# DevBit-MAX30102.net
KiCad netlist of a schematic drawn in EAGLE
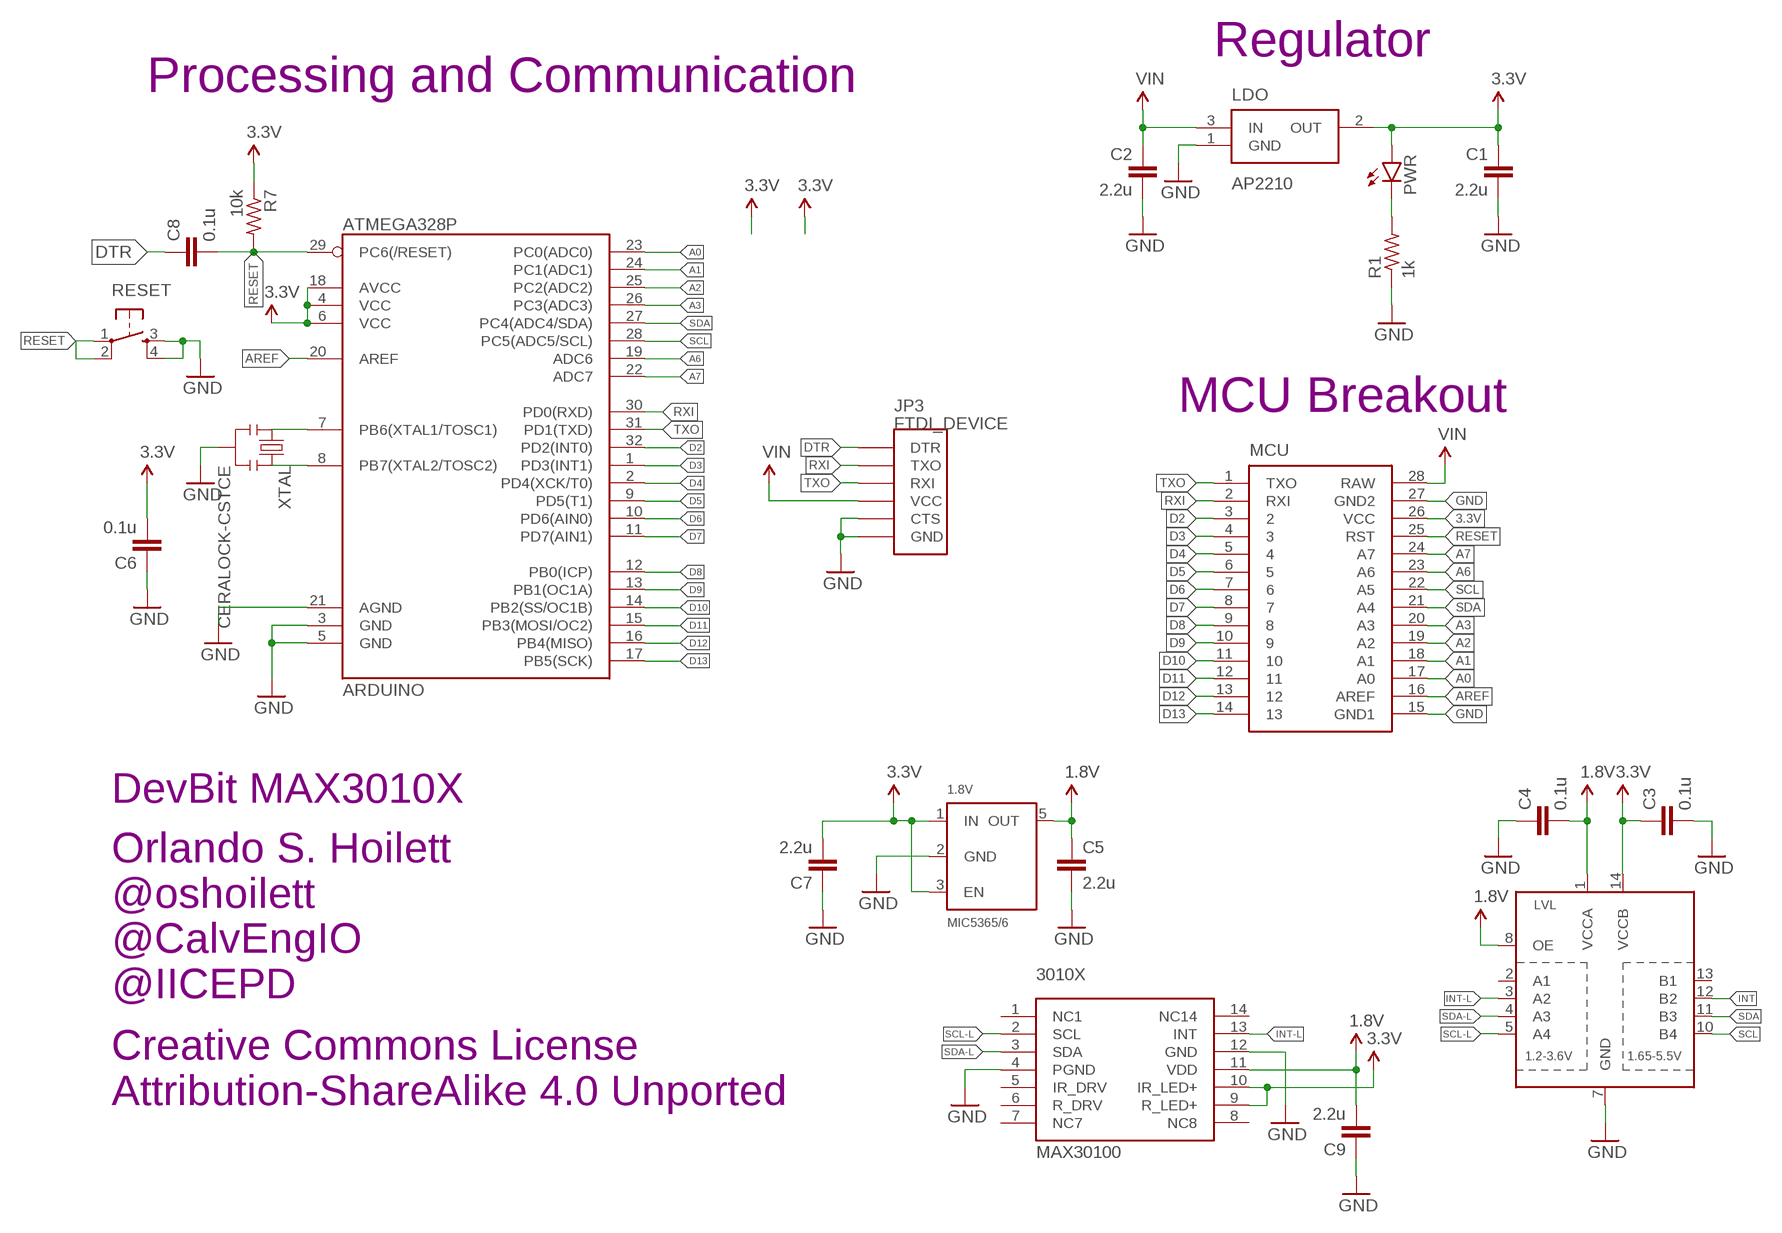
[diagram p0: schematic, sheet 1]

(export (version "E")
  (design (tool "Eeschema 10.0.6"))
  (components
    (comp (ref "1.8V")
      (value "MIC5365/6")
      (footprint "eagle-import:SC-70-5")
      (libsource (lib "eagle-import") (part "MIC5365/6"))
    )
    (comp (ref "3010X")
      (value "MAX30100")
      (footprint "eagle-import:OESIP14")
      (libsource (lib "eagle-import") (part "MAX30100"))
    )
    (comp (ref "ARDUINO")
      (value "ATMEGA328P")
      (footprint "eagle-import:TQFP32-08")
      (libsource (lib "eagle-import") (part "ATMEGA328_SMT-OHMOD"))
    )
    (comp (ref "C1")
      (value "2.2u")
      (footprint "eagle-import:C0402")
      (libsource (lib "eagle-import") (part "C-EUC0402"))
    )
    (comp (ref "C2")
      (value "2.2u")
      (footprint "eagle-import:C0402")
      (libsource (lib "eagle-import") (part "C-EUC0402"))
    )
    (comp (ref "C3")
      (value "0.1u")
      (footprint "eagle-import:C0402")
      (libsource (lib "eagle-import") (part "C-EUC0402"))
    )
    (comp (ref "C4")
      (value "0.1u")
      (footprint "eagle-import:C0402")
      (libsource (lib "eagle-import") (part "C-EUC0402"))
    )
    (comp (ref "C5")
      (value "2.2u")
      (footprint "eagle-import:C0402")
      (libsource (lib "eagle-import") (part "C-EUC0402"))
    )
    (comp (ref "C6")
      (value "0.1u")
      (footprint "eagle-import:C0402")
      (libsource (lib "eagle-import") (part "C-EUC0402"))
    )
    (comp (ref "C7")
      (value "2.2u")
      (footprint "eagle-import:C0402")
      (libsource (lib "eagle-import") (part "C-EUC0402"))
    )
    (comp (ref "C8")
      (value "0.1u")
      (footprint "eagle-import:C0402")
      (libsource (lib "eagle-import") (part "C-EUC0402"))
    )
    (comp (ref "C9")
      (value "2.2u")
      (footprint "eagle-import:C0402")
      (libsource (lib "eagle-import") (part "C-EUC0402"))
    )
    (comp (ref "JP3")
      (value "FTDI_DEVICE")
      (footprint "eagle-import:FTDI_DEVICE")
      (libsource (lib "eagle-import") (part "FTDI_DEVICE"))
    )
    (comp (ref "LDO")
      (value "AP2210")
      (footprint "eagle-import:SOT23")
      (libsource (lib "eagle-import") (part "AP2210"))
    )
    (comp (ref "LVL")
      (value "TXB0104PWR")
      (footprint "eagle-import:TSSOP14")
      (libsource (lib "eagle-import") (part "TXB0104PWR"))
    )
    (comp (ref "MCU")
      (value "DEVBASIC-V1")
      (footprint "eagle-import:DEVBIT-BASIC-V1")
      (libsource (lib "eagle-import") (part "DEVBASIC-V1"))
    )
    (comp (ref "PWR")
      (value "LED0603")
      (footprint "eagle-import:LED-0603")
      (libsource (lib "eagle-import") (part "LED0603"))
    )
    (comp (ref "R1")
      (value "1k")
      (footprint "eagle-import:R0402")
      (libsource (lib "eagle-import") (part "R-US_R0402"))
    )
    (comp (ref "R7")
      (value "10k")
      (footprint "eagle-import:R0402")
      (libsource (lib "eagle-import") (part "R-US_R0402"))
    )
    (comp (ref "RESET")
      (value "BUTTON-PTS830GG140")
      (footprint "eagle-import:BUTTON-GULLWING")
      (libsource (lib "eagle-import") (part "BUTTON-PTS830GG140"))
    )
    (comp (ref "XTAL")
      (value "CERALOCK-CSTCE")
      (footprint "eagle-import:RESONATOR-00")
      (libsource (lib "eagle-import") (part "CERALOCK-CSTCE"))
    )
  )
  (nets
    (net (code "1") (name "1.8V") (class "Default")
      (node (ref "1.8V") (pin "5") (pinfunction "OUT_5") (pintype "bidirectional"))
      (node (ref "3010X") (pin "11") (pinfunction "VDD_11") (pintype "bidirectional"))
      (node (ref "C4") (pin "2") (pinfunction "2_2") (pintype "passive"))
      (node (ref "C5") (pin "1") (pinfunction "1_1") (pintype "passive"))
      (node (ref "C9") (pin "2") (pinfunction "2_2") (pintype "passive"))
      (node (ref "LVL") (pin "1") (pinfunction "VCCA_1") (pintype "bidirectional"))
      (node (ref "LVL") (pin "8") (pinfunction "OE_8") (pintype "bidirectional"))
    )
    (net (code "2") (name "3.3V") (class "Default")
      (node (ref "1.8V") (pin "1") (pinfunction "IN_1") (pintype "bidirectional"))
      (node (ref "1.8V") (pin "3") (pinfunction "EN_3") (pintype "bidirectional"))
      (node (ref "3010X") (pin "10") (pinfunction "IR_LED+_10") (pintype "bidirectional"))
      (node (ref "3010X") (pin "9") (pinfunction "R_LED+_9") (pintype "bidirectional"))
      (node (ref "ARDUINO") (pin "18") (pinfunction "AVCC_18") (pintype "bidirectional"))
      (node (ref "ARDUINO") (pin "4") (pinfunction "VCC_4") (pintype "bidirectional"))
      (node (ref "ARDUINO") (pin "6") (pinfunction "VCC_6") (pintype "bidirectional"))
      (node (ref "C1") (pin "1") (pinfunction "1_1") (pintype "passive"))
      (node (ref "C3") (pin "1") (pinfunction "1_1") (pintype "passive"))
      (node (ref "C6") (pin "2") (pinfunction "2_2") (pintype "passive"))
      (node (ref "C7") (pin "2") (pinfunction "2_2") (pintype "passive"))
      (node (ref "LDO") (pin "2") (pinfunction "OUT_2") (pintype "bidirectional"))
      (node (ref "LVL") (pin "14") (pinfunction "VCCB_14") (pintype "bidirectional"))
      (node (ref "MCU") (pin "26") (pinfunction "VCC_26") (pintype "bidirectional"))
      (node (ref "PWR") (pin "A") (pinfunction "A_A") (pintype "passive"))
      (node (ref "R7") (pin "1") (pinfunction "1_1") (pintype "passive"))
    )
    (net (code "3") (name "A0") (class "Default")
      (node (ref "ARDUINO") (pin "23") (pinfunction "PC0(ADC0)_23") (pintype "bidirectional"))
      (node (ref "MCU") (pin "17") (pinfunction "A0_17") (pintype "bidirectional"))
    )
    (net (code "4") (name "A1") (class "Default")
      (node (ref "ARDUINO") (pin "24") (pinfunction "PC1(ADC1)_24") (pintype "bidirectional"))
      (node (ref "MCU") (pin "18") (pinfunction "A1_18") (pintype "bidirectional"))
    )
    (net (code "5") (name "A2") (class "Default")
      (node (ref "ARDUINO") (pin "25") (pinfunction "PC2(ADC2)_25") (pintype "bidirectional"))
      (node (ref "MCU") (pin "19") (pinfunction "A2_19") (pintype "bidirectional"))
    )
    (net (code "6") (name "A3") (class "Default")
      (node (ref "ARDUINO") (pin "26") (pinfunction "PC3(ADC3)_26") (pintype "bidirectional"))
      (node (ref "MCU") (pin "20") (pinfunction "A3_20") (pintype "bidirectional"))
    )
    (net (code "7") (name "A6") (class "Default")
      (node (ref "ARDUINO") (pin "19") (pinfunction "ADC6_19") (pintype "bidirectional"))
      (node (ref "MCU") (pin "23") (pinfunction "A6_23") (pintype "bidirectional"))
    )
    (net (code "8") (name "A7") (class "Default")
      (node (ref "ARDUINO") (pin "22") (pinfunction "ADC7_22") (pintype "bidirectional"))
      (node (ref "MCU") (pin "24") (pinfunction "A7_24") (pintype "bidirectional"))
    )
    (net (code "9") (name "AREF") (class "Default")
      (node (ref "ARDUINO") (pin "20") (pinfunction "AREF_20") (pintype "bidirectional"))
      (node (ref "MCU") (pin "16") (pinfunction "AREF_16") (pintype "bidirectional"))
    )
    (net (code "10") (name "D2") (class "Default")
      (node (ref "ARDUINO") (pin "32") (pinfunction "PD2(INT0)_32") (pintype "bidirectional"))
      (node (ref "MCU") (pin "3") (pinfunction "2_3") (pintype "bidirectional"))
    )
    (net (code "11") (name "D3") (class "Default")
      (node (ref "ARDUINO") (pin "1") (pinfunction "PD3(INT1)_1") (pintype "bidirectional"))
      (node (ref "MCU") (pin "4") (pinfunction "3_4") (pintype "bidirectional"))
    )
    (net (code "12") (name "D4") (class "Default")
      (node (ref "ARDUINO") (pin "2") (pinfunction "PD4(XCK/T0)_2") (pintype "bidirectional"))
      (node (ref "MCU") (pin "5") (pinfunction "4_5") (pintype "bidirectional"))
    )
    (net (code "13") (name "D5") (class "Default")
      (node (ref "ARDUINO") (pin "9") (pinfunction "PD5(T1)_9") (pintype "bidirectional"))
      (node (ref "MCU") (pin "6") (pinfunction "5_6") (pintype "bidirectional"))
    )
    (net (code "14") (name "D6") (class "Default")
      (node (ref "ARDUINO") (pin "10") (pinfunction "PD6(AIN0)_10") (pintype "bidirectional"))
      (node (ref "MCU") (pin "7") (pinfunction "6_7") (pintype "bidirectional"))
    )
    (net (code "15") (name "D7") (class "Default")
      (node (ref "ARDUINO") (pin "11") (pinfunction "PD7(AIN1)_11") (pintype "bidirectional"))
      (node (ref "MCU") (pin "8") (pinfunction "7_8") (pintype "bidirectional"))
    )
    (net (code "16") (name "D8") (class "Default")
      (node (ref "ARDUINO") (pin "12") (pinfunction "PB0(ICP)_12") (pintype "bidirectional"))
      (node (ref "MCU") (pin "9") (pinfunction "8_9") (pintype "bidirectional"))
    )
    (net (code "17") (name "D9") (class "Default")
      (node (ref "ARDUINO") (pin "13") (pinfunction "PB1(OC1A)_13") (pintype "bidirectional"))
      (node (ref "MCU") (pin "10") (pinfunction "9_10") (pintype "bidirectional"))
    )
    (net (code "18") (name "D10") (class "Default")
      (node (ref "ARDUINO") (pin "14") (pinfunction "PB2(SS/OC1B)_14") (pintype "bidirectional"))
      (node (ref "MCU") (pin "11") (pinfunction "10_11") (pintype "bidirectional"))
    )
    (net (code "19") (name "D11") (class "Default")
      (node (ref "ARDUINO") (pin "15") (pinfunction "PB3(MOSI/OC2)_15") (pintype "bidirectional"))
      (node (ref "MCU") (pin "12") (pinfunction "11_12") (pintype "bidirectional"))
    )
    (net (code "20") (name "D12") (class "Default")
      (node (ref "ARDUINO") (pin "16") (pinfunction "PB4(MISO)_16") (pintype "bidirectional"))
      (node (ref "MCU") (pin "13") (pinfunction "12_13") (pintype "bidirectional"))
    )
    (net (code "21") (name "D13") (class "Default")
      (node (ref "ARDUINO") (pin "17") (pinfunction "PB5(SCK)_17") (pintype "bidirectional"))
      (node (ref "MCU") (pin "14") (pinfunction "13_14") (pintype "bidirectional"))
    )
    (net (code "22") (name "DTR") (class "Default")
      (node (ref "C8") (pin "1") (pinfunction "1_1") (pintype "passive"))
      (node (ref "JP3") (pin "DTR") (pinfunction "DTR_DTR") (pintype "bidirectional"))
    )
    (net (code "23") (name "GND") (class "Default")
      (node (ref "1.8V") (pin "2") (pinfunction "GND_2") (pintype "bidirectional"))
      (node (ref "3010X") (pin "12") (pinfunction "GND_12") (pintype "bidirectional"))
      (node (ref "3010X") (pin "4") (pinfunction "PGND_4") (pintype "bidirectional"))
      (node (ref "ARDUINO") (pin "21") (pinfunction "AGND_21") (pintype "bidirectional"))
      (node (ref "ARDUINO") (pin "3") (pinfunction "GND_3") (pintype "bidirectional"))
      (node (ref "ARDUINO") (pin "5") (pinfunction "GND_5") (pintype "bidirectional"))
      (node (ref "C1") (pin "2") (pinfunction "2_2") (pintype "passive"))
      (node (ref "C2") (pin "2") (pinfunction "2_2") (pintype "passive"))
      (node (ref "C3") (pin "2") (pinfunction "2_2") (pintype "passive"))
      (node (ref "C4") (pin "1") (pinfunction "1_1") (pintype "passive"))
      (node (ref "C5") (pin "2") (pinfunction "2_2") (pintype "passive"))
      (node (ref "C6") (pin "1") (pinfunction "1_1") (pintype "passive"))
      (node (ref "C7") (pin "1") (pinfunction "1_1") (pintype "passive"))
      (node (ref "C9") (pin "1") (pinfunction "1_1") (pintype "passive"))
      (node (ref "JP3") (pin "CTS") (pinfunction "CTS_CTS") (pintype "bidirectional"))
      (node (ref "JP3") (pin "GND") (pinfunction "GND_GND") (pintype "bidirectional"))
      (node (ref "LDO") (pin "1") (pinfunction "GND_1") (pintype "bidirectional"))
      (node (ref "LVL") (pin "7") (pinfunction "GND_7") (pintype "bidirectional"))
      (node (ref "MCU") (pin "15") (pinfunction "GND1_15") (pintype "bidirectional"))
      (node (ref "MCU") (pin "27") (pinfunction "GND2_27") (pintype "bidirectional"))
      (node (ref "R1") (pin "1") (pinfunction "1_1") (pintype "passive"))
      (node (ref "RESET") (pin "3") (pinfunction "3_3") (pintype "passive"))
      (node (ref "RESET") (pin "4") (pinfunction "4_4") (pintype "passive"))
      (node (ref "XTAL") (pin "2") (pinfunction "2_2") (pintype "passive"))
    )
    (net (code "24") (name "INT") (class "Default")
      (node (ref "LVL") (pin "12") (pinfunction "B2_12") (pintype "bidirectional"))
    )
    (net (code "25") (name "INT-L") (class "Default")
      (node (ref "3010X") (pin "13") (pinfunction "INT_13") (pintype "bidirectional"))
      (node (ref "LVL") (pin "3") (pinfunction "A2_3") (pintype "bidirectional"))
    )
    (net (code "26") (name "Net-(ARDUINO-PB6(XTAL1{slash}TOSC1))") (class "Default")
      (node (ref "ARDUINO") (pin "7") (pinfunction "PB6(XTAL1/TOSC1)_7") (pintype "bidirectional"))
      (node (ref "XTAL") (pin "1") (pinfunction "1_1") (pintype "passive"))
    )
    (net (code "27") (name "Net-(ARDUINO-PB7(XTAL2{slash}TOSC2))") (class "Default")
      (node (ref "ARDUINO") (pin "8") (pinfunction "PB7(XTAL2/TOSC2)_8") (pintype "bidirectional"))
      (node (ref "XTAL") (pin "3") (pinfunction "3_3") (pintype "passive"))
    )
    (net (code "28") (name "Net-(PWR-PadC)") (class "Default")
      (node (ref "PWR") (pin "C") (pinfunction "C_C") (pintype "passive"))
      (node (ref "R1") (pin "2") (pinfunction "2_2") (pintype "passive"))
    )
    (net (code "29") (name "RESET") (class "Default")
      (node (ref "ARDUINO") (pin "29") (pinfunction "PC6(/RESET)_29") (pintype "bidirectional"))
      (node (ref "C8") (pin "2") (pinfunction "2_2") (pintype "passive"))
      (node (ref "MCU") (pin "25") (pinfunction "RST_25") (pintype "bidirectional"))
      (node (ref "R7") (pin "2") (pinfunction "2_2") (pintype "passive"))
      (node (ref "RESET") (pin "1") (pinfunction "1_1") (pintype "passive"))
      (node (ref "RESET") (pin "2") (pinfunction "2_2") (pintype "passive"))
    )
    (net (code "30") (name "RXI") (class "Default")
      (node (ref "ARDUINO") (pin "30") (pinfunction "PD0(RXD)_30") (pintype "bidirectional"))
      (node (ref "JP3") (pin "TXO") (pinfunction "TXO_TXO") (pintype "bidirectional"))
      (node (ref "MCU") (pin "2") (pinfunction "RXI_2") (pintype "bidirectional"))
    )
    (net (code "31") (name "SCL") (class "Default")
      (node (ref "ARDUINO") (pin "28") (pinfunction "PC5(ADC5/SCL)_28") (pintype "bidirectional"))
      (node (ref "LVL") (pin "10") (pinfunction "B4_10") (pintype "bidirectional"))
      (node (ref "MCU") (pin "22") (pinfunction "A5_22") (pintype "bidirectional"))
    )
    (net (code "32") (name "SCL-L") (class "Default")
      (node (ref "3010X") (pin "2") (pinfunction "SCL_2") (pintype "bidirectional"))
      (node (ref "LVL") (pin "5") (pinfunction "A4_5") (pintype "bidirectional"))
    )
    (net (code "33") (name "SDA") (class "Default")
      (node (ref "ARDUINO") (pin "27") (pinfunction "PC4(ADC4/SDA)_27") (pintype "bidirectional"))
      (node (ref "LVL") (pin "11") (pinfunction "B3_11") (pintype "bidirectional"))
      (node (ref "MCU") (pin "21") (pinfunction "A4_21") (pintype "bidirectional"))
    )
    (net (code "34") (name "SDA-L") (class "Default")
      (node (ref "3010X") (pin "3") (pinfunction "SDA_3") (pintype "bidirectional"))
      (node (ref "LVL") (pin "4") (pinfunction "A3_4") (pintype "bidirectional"))
    )
    (net (code "35") (name "TXO") (class "Default")
      (node (ref "ARDUINO") (pin "31") (pinfunction "PD1(TXD)_31") (pintype "bidirectional"))
      (node (ref "JP3") (pin "RXI") (pinfunction "RXI_RXI") (pintype "bidirectional"))
      (node (ref "MCU") (pin "1") (pinfunction "TXO_1") (pintype "bidirectional"))
    )
    (net (code "36") (name "VIN") (class "Default")
      (node (ref "C2") (pin "1") (pinfunction "1_1") (pintype "passive"))
      (node (ref "JP3") (pin "VCC") (pinfunction "VCC_VCC") (pintype "bidirectional"))
      (node (ref "LDO") (pin "3") (pinfunction "IN_3") (pintype "bidirectional"))
      (node (ref "MCU") (pin "28") (pinfunction "RAW_28") (pintype "bidirectional"))
    )
    (net (code "37") (name "unconnected-(3010X-IR_DRV-Pad5)") (class "Default")
      (node (ref "3010X") (pin "5") (pinfunction "IR_DRV_5") (pintype "bidirectional"))
    )
    (net (code "38") (name "unconnected-(3010X-NC1-Pad1)") (class "Default")
      (node (ref "3010X") (pin "1") (pinfunction "NC1_1") (pintype "bidirectional"))
    )
    (net (code "39") (name "unconnected-(3010X-NC7-Pad7)") (class "Default")
      (node (ref "3010X") (pin "7") (pinfunction "NC7_7") (pintype "bidirectional"))
    )
    (net (code "40") (name "unconnected-(3010X-NC8-Pad8)") (class "Default")
      (node (ref "3010X") (pin "8") (pinfunction "NC8_8") (pintype "bidirectional"))
    )
    (net (code "41") (name "unconnected-(3010X-NC14-Pad14)") (class "Default")
      (node (ref "3010X") (pin "14") (pinfunction "NC14_14") (pintype "bidirectional"))
    )
    (net (code "42") (name "unconnected-(3010X-R_DRV-Pad6)") (class "Default")
      (node (ref "3010X") (pin "6") (pinfunction "R_DRV_6") (pintype "bidirectional"))
    )
    (net (code "43") (name "unconnected-(LVL-A1-Pad2)") (class "Default")
      (node (ref "LVL") (pin "2") (pinfunction "A1_2") (pintype "bidirectional"))
    )
    (net (code "44") (name "unconnected-(LVL-B1-Pad13)") (class "Default")
      (node (ref "LVL") (pin "13") (pinfunction "B1_13") (pintype "bidirectional"))
    )
  )
)
